# Sheet1.net
KiCad netlist of a schematic drawn in Altium Designer
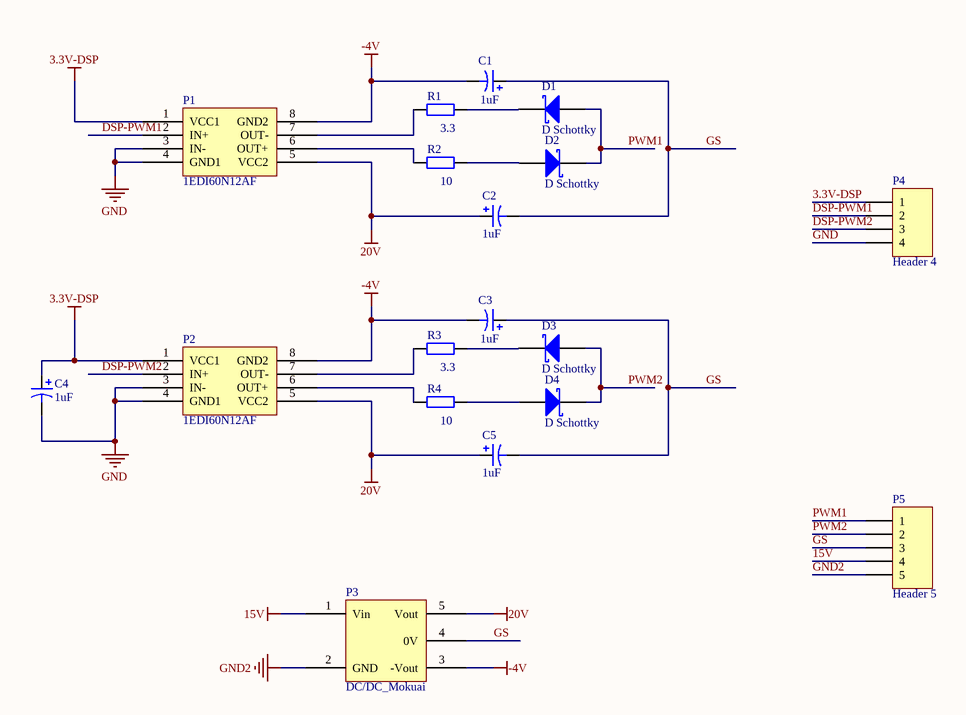
[diagram p0: Sheet1.SchDoc]

(export (version "E")
  (design (tool "Eeschema 10.0.6"))
  (components
    (comp (ref "C1")
      (value "1uF")
      (footprint "C-10uF")
      (description "Polarized Capacitor (Radial)")
      (fields (field (name "Comment") "Cap Pol1") (field (name "PUBLISHER") "Altium Limited"))
      (libsource (lib "Miscellaneous Devices") (part "Cap Pol1"))
    )
    (comp (ref "C2")
      (value "1uF")
      (footprint "C-10uF")
      (description "Polarized Capacitor (Radial)")
      (fields (field (name "Comment") "Cap Pol1") (field (name "PUBLISHER") "Altium Limited"))
      (libsource (lib "Miscellaneous Devices") (part "Cap Pol1"))
    )
    (comp (ref "C3")
      (value "1uF")
      (footprint "C-10uF")
      (description "Polarized Capacitor (Radial)")
      (fields (field (name "Comment") "Cap Pol1") (field (name "PUBLISHER") "Altium Limited"))
      (libsource (lib "Miscellaneous Devices") (part "Cap Pol1"))
    )
    (comp (ref "C4")
      (value "1uF")
      (footprint "C-10uF")
      (description "Polarized Capacitor (Radial)")
      (fields (field (name "Comment") "Cap Pol1") (field (name "PUBLISHER") "Altium Limited"))
      (libsource (lib "Miscellaneous Devices") (part "Cap Pol1"))
    )
    (comp (ref "C5")
      (value "1uF")
      (footprint "C-10uF")
      (description "Polarized Capacitor (Radial)")
      (fields (field (name "Comment") "Cap Pol1") (field (name "PUBLISHER") "Altium Limited"))
      (libsource (lib "Miscellaneous Devices") (part "Cap Pol1"))
    )
    (comp (ref "D1")
      (value "D Schottky")
      (footprint "Diode")
      (description "Schottky Diode")
      (fields (field (name "PUBLISHER") "Altium Limited"))
      (libsource (lib "Miscellaneous Devices") (part "D Schottky"))
    )
    (comp (ref "D2")
      (value "D Schottky")
      (footprint "Diode")
      (description "Schottky Diode")
      (fields (field (name "PUBLISHER") "Altium Limited"))
      (libsource (lib "Miscellaneous Devices") (part "D Schottky"))
    )
    (comp (ref "D3")
      (value "D Schottky")
      (footprint "Diode")
      (description "Schottky Diode")
      (fields (field (name "PUBLISHER") "Altium Limited"))
      (libsource (lib "Miscellaneous Devices") (part "D Schottky"))
    )
    (comp (ref "D4")
      (value "D Schottky")
      (footprint "Diode")
      (description "Schottky Diode")
      (fields (field (name "PUBLISHER") "Altium Limited"))
      (libsource (lib "Miscellaneous Devices") (part "D Schottky"))
    )
    (comp (ref "P1")
      (value "1EDI60N12AF")
      (footprint "sop-8")
      (libsource (lib "sharing") (part "1EDI60N12AF"))
    )
    (comp (ref "P2")
      (value "1EDI60N12AF")
      (footprint "sop-8")
      (libsource (lib "sharing") (part "1EDI60N12AF"))
    )
    (comp (ref "P3")
      (value "DC/DC_Mokuai")
      (footprint "DC/DC_MoKuai")
      (libsource (lib "sharing_Library1") (part "DC/DC_Mokuai"))
    )
    (comp (ref "P4")
      (value "Header 4")
      (footprint "4_DuanZi")
      (description "Header, 4-Pin")
      (fields (field (name "PUBLISHER") "Altium Limited"))
      (libsource (lib "Miscellaneous Connectors") (part "Header 4"))
    )
    (comp (ref "P5")
      (value "Header 5")
      (footprint "5_DuanZi")
      (description "Header, 5-Pin")
      (fields (field (name "PUBLISHER") "Altium Limited"))
      (libsource (lib "Miscellaneous Connectors") (part "Header 5"))
    )
    (comp (ref "R1")
      (value "3.3")
      (footprint "AXIAL-0.4")
      (description "Resistor")
      (fields (field (name "Comment") "Res2") (field (name "PUBLISHER") "Altium Limited"))
      (libsource (lib "Miscellaneous Devices") (part "Res2"))
    )
    (comp (ref "R2")
      (value "10")
      (footprint "AXIAL-0.4")
      (description "Resistor")
      (fields (field (name "Comment") "Res2") (field (name "PUBLISHER") "Altium Limited"))
      (libsource (lib "Miscellaneous Devices") (part "Res2"))
    )
    (comp (ref "R3")
      (value "3.3")
      (footprint "AXIAL-0.4")
      (description "Resistor")
      (fields (field (name "Comment") "Res2") (field (name "PUBLISHER") "Altium Limited"))
      (libsource (lib "Miscellaneous Devices") (part "Res2"))
    )
    (comp (ref "R4")
      (value "10")
      (footprint "AXIAL-0.4")
      (description "Resistor")
      (fields (field (name "Comment") "Res2") (field (name "PUBLISHER") "Altium Limited"))
      (libsource (lib "Miscellaneous Devices") (part "Res2"))
    )
  )
  (nets
    (net (code "1") (name "-4V") (class "Default")
      (node (ref "C1") (pin "2") (pinfunction "2_2") (pintype "passive"))
      (node (ref "C3") (pin "2") (pinfunction "2_2") (pintype "passive"))
      (node (ref "P1") (pin "8") (pinfunction "GND2_8") (pintype "passive"))
      (node (ref "P2") (pin "8") (pinfunction "GND2_8") (pintype "passive"))
      (node (ref "P3") (pin "3") (pinfunction "-Vout_3") (pintype "passive"))
    )
    (net (code "2") (name "/DSP-PWM1") (class "Default")
      (node (ref "P1") (pin "2") (pinfunction "IN+_2") (pintype "passive"))
      (node (ref "P4") (pin "2") (pinfunction "2_2") (pintype "passive"))
    )
    (net (code "3") (name "/DSP-PWM2") (class "Default")
      (node (ref "P2") (pin "2") (pinfunction "IN+_2") (pintype "passive"))
      (node (ref "P4") (pin "3") (pinfunction "3_3") (pintype "passive"))
    )
    (net (code "4") (name "/GS") (class "Default")
      (node (ref "C1") (pin "1") (pinfunction "1_1") (pintype "passive"))
      (node (ref "C2") (pin "2") (pinfunction "2_2") (pintype "passive"))
      (node (ref "C3") (pin "1") (pinfunction "1_1") (pintype "passive"))
      (node (ref "C5") (pin "2") (pinfunction "2_2") (pintype "passive"))
      (node (ref "P3") (pin "4") (pinfunction "0V_4") (pintype "passive"))
      (node (ref "P5") (pin "3") (pinfunction "3_3") (pintype "passive"))
    )
    (net (code "5") (name "/PWM1") (class "Default")
      (node (ref "D1") (pin "1") (pinfunction "A_1") (pintype "passive"))
      (node (ref "D2") (pin "2") (pinfunction "K_2") (pintype "passive"))
      (node (ref "P5") (pin "1") (pinfunction "1_1") (pintype "passive"))
    )
    (net (code "6") (name "/PWM2") (class "Default")
      (node (ref "D3") (pin "1") (pinfunction "A_1") (pintype "passive"))
      (node (ref "D4") (pin "2") (pinfunction "K_2") (pintype "passive"))
      (node (ref "P5") (pin "2") (pinfunction "2_2") (pintype "passive"))
    )
    (net (code "7") (name "3.3V-DSP") (class "Default")
      (node (ref "C4") (pin "1") (pinfunction "1_1") (pintype "passive"))
      (node (ref "P1") (pin "1") (pinfunction "VCC1_1") (pintype "passive"))
      (node (ref "P2") (pin "1") (pinfunction "VCC1_1") (pintype "passive"))
      (node (ref "P4") (pin "1") (pinfunction "1_1") (pintype "passive"))
    )
    (net (code "8") (name "15V") (class "Default")
      (node (ref "P3") (pin "1") (pinfunction "Vin_1") (pintype "passive"))
      (node (ref "P5") (pin "4") (pinfunction "4_4") (pintype "passive"))
    )
    (net (code "9") (name "20V") (class "Default")
      (node (ref "C2") (pin "1") (pinfunction "1_1") (pintype "passive"))
      (node (ref "C5") (pin "1") (pinfunction "1_1") (pintype "passive"))
      (node (ref "P1") (pin "5") (pinfunction "VCC2_5") (pintype "passive"))
      (node (ref "P2") (pin "5") (pinfunction "VCC2_5") (pintype "passive"))
      (node (ref "P3") (pin "5") (pinfunction "Vout_5") (pintype "passive"))
    )
    (net (code "10") (name "GND") (class "Default")
      (node (ref "C4") (pin "2") (pinfunction "2_2") (pintype "passive"))
      (node (ref "P1") (pin "3") (pinfunction "IN-_3") (pintype "passive"))
      (node (ref "P1") (pin "4") (pinfunction "GND1_4") (pintype "passive"))
      (node (ref "P2") (pin "3") (pinfunction "IN-_3") (pintype "passive"))
      (node (ref "P2") (pin "4") (pinfunction "GND1_4") (pintype "passive"))
      (node (ref "P4") (pin "4") (pinfunction "4_4") (pintype "passive"))
    )
    (net (code "11") (name "GND2") (class "Default")
      (node (ref "P3") (pin "2") (pinfunction "GND_2") (pintype "passive"))
      (node (ref "P5") (pin "5") (pinfunction "5_5") (pintype "passive"))
    )
    (net (code "12") (name "Net-(D1-K)") (class "Default")
      (node (ref "D1") (pin "2") (pinfunction "K_2") (pintype "passive"))
      (node (ref "R1") (pin "2") (pinfunction "2_2") (pintype "passive"))
    )
    (net (code "13") (name "Net-(D2-A)") (class "Default")
      (node (ref "D2") (pin "1") (pinfunction "A_1") (pintype "passive"))
      (node (ref "R2") (pin "2") (pinfunction "2_2") (pintype "passive"))
    )
    (net (code "14") (name "Net-(D3-K)") (class "Default")
      (node (ref "D3") (pin "2") (pinfunction "K_2") (pintype "passive"))
      (node (ref "R3") (pin "2") (pinfunction "2_2") (pintype "passive"))
    )
    (net (code "15") (name "Net-(D4-A)") (class "Default")
      (node (ref "D4") (pin "1") (pinfunction "A_1") (pintype "passive"))
      (node (ref "R4") (pin "2") (pinfunction "2_2") (pintype "passive"))
    )
    (net (code "16") (name "Net-(P1-OUT+)") (class "Default")
      (node (ref "P1") (pin "6") (pinfunction "OUT+_6") (pintype "passive"))
      (node (ref "R2") (pin "1") (pinfunction "1_1") (pintype "passive"))
    )
    (net (code "17") (name "Net-(P1-OUT-)") (class "Default")
      (node (ref "P1") (pin "7") (pinfunction "OUT-_7") (pintype "passive"))
      (node (ref "R1") (pin "1") (pinfunction "1_1") (pintype "passive"))
    )
    (net (code "18") (name "Net-(P2-OUT+)") (class "Default")
      (node (ref "P2") (pin "6") (pinfunction "OUT+_6") (pintype "passive"))
      (node (ref "R4") (pin "1") (pinfunction "1_1") (pintype "passive"))
    )
    (net (code "19") (name "Net-(P2-OUT-)") (class "Default")
      (node (ref "P2") (pin "7") (pinfunction "OUT-_7") (pintype "passive"))
      (node (ref "R3") (pin "1") (pinfunction "1_1") (pintype "passive"))
    )
  )
)
